# LDR.net
KiCad netlist of a schematic drawn in EAGLE
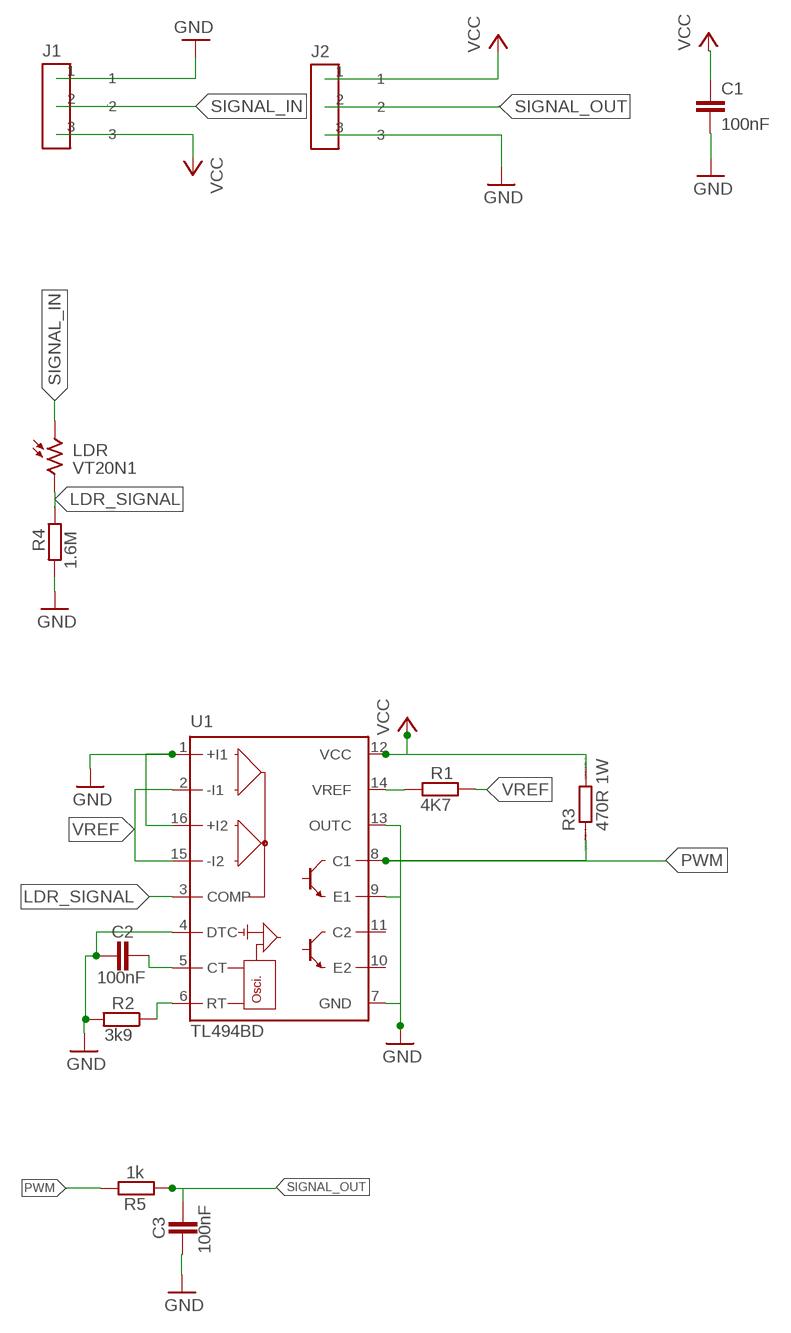
[diagram p0: schematic, sheet 1]

(export (version "E")
  (design (tool "Eeschema 10.0.6"))
  (components
    (comp (ref "C1")
      (value "100nF")
      (footprint "eagle-import:C0805")
      (libsource (lib "eagle-import") (part "C-EUC0805"))
    )
    (comp (ref "C2")
      (value "100nF")
      (footprint "eagle-import:C0805")
      (libsource (lib "eagle-import") (part "C-EUC0805"))
    )
    (comp (ref "C3")
      (value "100nF")
      (footprint "eagle-import:C0805")
      (libsource (lib "eagle-import") (part "C-EUC0805"))
    )
    (comp (ref "J1")
      (value "CONECTOR_MACHO")
      (footprint "eagle-import:MALE")
      (libsource (lib "eagle-import") (part "CONECTOR_MACHO"))
    )
    (comp (ref "J2")
      (value "CONECTOR_FEMEA")
      (footprint "eagle-import:FEMALE")
      (libsource (lib "eagle-import") (part "CONECTOR_FEMEA"))
    )
    (comp (ref "LDR")
      (value "VT20N1")
      (footprint "eagle-import:TO46-VT200")
      (libsource (lib "eagle-import") (part "VT20N1"))
    )
    (comp (ref "R1")
      (value "4K7")
      (footprint "eagle-import:R0805W")
      (libsource (lib "eagle-import") (part "R-EU_R0805W"))
    )
    (comp (ref "R2")
      (value "3k9")
      (footprint "eagle-import:R0805W")
      (libsource (lib "eagle-import") (part "R-EU_R0805W"))
    )
    (comp (ref "R3")
      (value "470R 1W")
      (footprint "eagle-import:R2512")
      (libsource (lib "eagle-import") (part "RR2512"))
    )
    (comp (ref "R4")
      (value "1.6M")
      (footprint "eagle-import:R0805W")
      (libsource (lib "eagle-import") (part "R-EU_R0805W"))
    )
    (comp (ref "R5")
      (value "1k")
      (footprint "eagle-import:R0805W")
      (libsource (lib "eagle-import") (part "R-EU_R0805W"))
    )
    (comp (ref "U1")
      (value "TL494BD")
      (footprint "eagle-import:SO16")
      (libsource (lib "eagle-import") (part "TL494DB"))
    )
  )
  (nets
    (net (code "1") (name "GND") (class "Default")
      (node (ref "C1") (pin "2") (pinfunction "2_2") (pintype "passive"))
      (node (ref "C2") (pin "1") (pinfunction "1_1") (pintype "passive"))
      (node (ref "C3") (pin "1") (pinfunction "1_1") (pintype "passive"))
      (node (ref "J1") (pin "1") (pinfunction "1_1") (pintype "bidirectional"))
      (node (ref "J2") (pin "3") (pinfunction "3_3") (pintype "bidirectional"))
      (node (ref "R2") (pin "2") (pinfunction "2_2") (pintype "passive"))
      (node (ref "R4") (pin "2") (pinfunction "2_2") (pintype "passive"))
      (node (ref "U1") (pin "1") (pinfunction "+I1_1") (pintype "input"))
      (node (ref "U1") (pin "13") (pinfunction "OUTC_13") (pintype "output"))
      (node (ref "U1") (pin "16") (pinfunction "+I2_16") (pintype "input"))
      (node (ref "U1") (pin "4") (pinfunction "DTC_4") (pintype "input"))
      (node (ref "U1") (pin "7") (pinfunction "GND_7") (pintype "power_in"))
      (node (ref "U1") (pin "9") (pinfunction "E1_9") (pintype "passive"))
    )
    (net (code "2") (name "LDR_SIGNAL") (class "Default")
      (node (ref "LDR") (pin "2") (pinfunction "2_2") (pintype "passive"))
      (node (ref "R4") (pin "1") (pinfunction "1_1") (pintype "passive"))
      (node (ref "U1") (pin "3") (pinfunction "COMP_3") (pintype "passive"))
    )
    (net (code "3") (name "Net-(U1-CT)") (class "Default")
      (node (ref "C2") (pin "2") (pinfunction "2_2") (pintype "passive"))
      (node (ref "U1") (pin "5") (pinfunction "CT_5") (pintype "input"))
    )
    (net (code "4") (name "Net-(U1-RT)") (class "Default")
      (node (ref "R2") (pin "1") (pinfunction "1_1") (pintype "passive"))
      (node (ref "U1") (pin "6") (pinfunction "RT_6") (pintype "input"))
    )
    (net (code "5") (name "Net-(U1-VREF)") (class "Default")
      (node (ref "R1") (pin "2") (pinfunction "2_2") (pintype "passive"))
      (node (ref "U1") (pin "14") (pinfunction "VREF_14") (pintype "input"))
    )
    (net (code "6") (name "PWM") (class "Default")
      (node (ref "R3") (pin "1") (pinfunction "1_1") (pintype "passive"))
      (node (ref "R5") (pin "1") (pinfunction "1_1") (pintype "passive"))
      (node (ref "U1") (pin "8") (pinfunction "C1_8") (pintype "passive"))
    )
    (net (code "7") (name "SIGNAL_IN") (class "Default")
      (node (ref "J1") (pin "2") (pinfunction "2_2") (pintype "bidirectional"))
      (node (ref "LDR") (pin "1") (pinfunction "1_1") (pintype "passive"))
    )
    (net (code "8") (name "SIGNAL_OUT") (class "Default")
      (node (ref "C3") (pin "2") (pinfunction "2_2") (pintype "passive"))
      (node (ref "J2") (pin "2") (pinfunction "2_2") (pintype "bidirectional"))
      (node (ref "R5") (pin "2") (pinfunction "2_2") (pintype "passive"))
    )
    (net (code "9") (name "VCC") (class "Default")
      (node (ref "C1") (pin "1") (pinfunction "1_1") (pintype "passive"))
      (node (ref "J1") (pin "3") (pinfunction "3_3") (pintype "bidirectional"))
      (node (ref "J2") (pin "1") (pinfunction "1_1") (pintype "bidirectional"))
      (node (ref "R3") (pin "2") (pinfunction "2_2") (pintype "passive"))
      (node (ref "U1") (pin "12") (pinfunction "VCC_12") (pintype "power_in"))
    )
    (net (code "10") (name "VREF") (class "Default")
      (node (ref "R1") (pin "1") (pinfunction "1_1") (pintype "passive"))
      (node (ref "U1") (pin "15") (pinfunction "-I2_15") (pintype "input"))
      (node (ref "U1") (pin "2") (pinfunction "-I1_2") (pintype "input"))
    )
    (net (code "11") (name "unconnected-(U1-C2-Pad11)") (class "Default")
      (node (ref "U1") (pin "11") (pinfunction "C2_11") (pintype "passive"))
    )
    (net (code "12") (name "unconnected-(U1-E2-Pad10)") (class "Default")
      (node (ref "U1") (pin "10") (pinfunction "E2_10") (pintype "passive"))
    )
  )
)
